# audio.net
KiCad netlist of a schematic drawn in Altium Designer
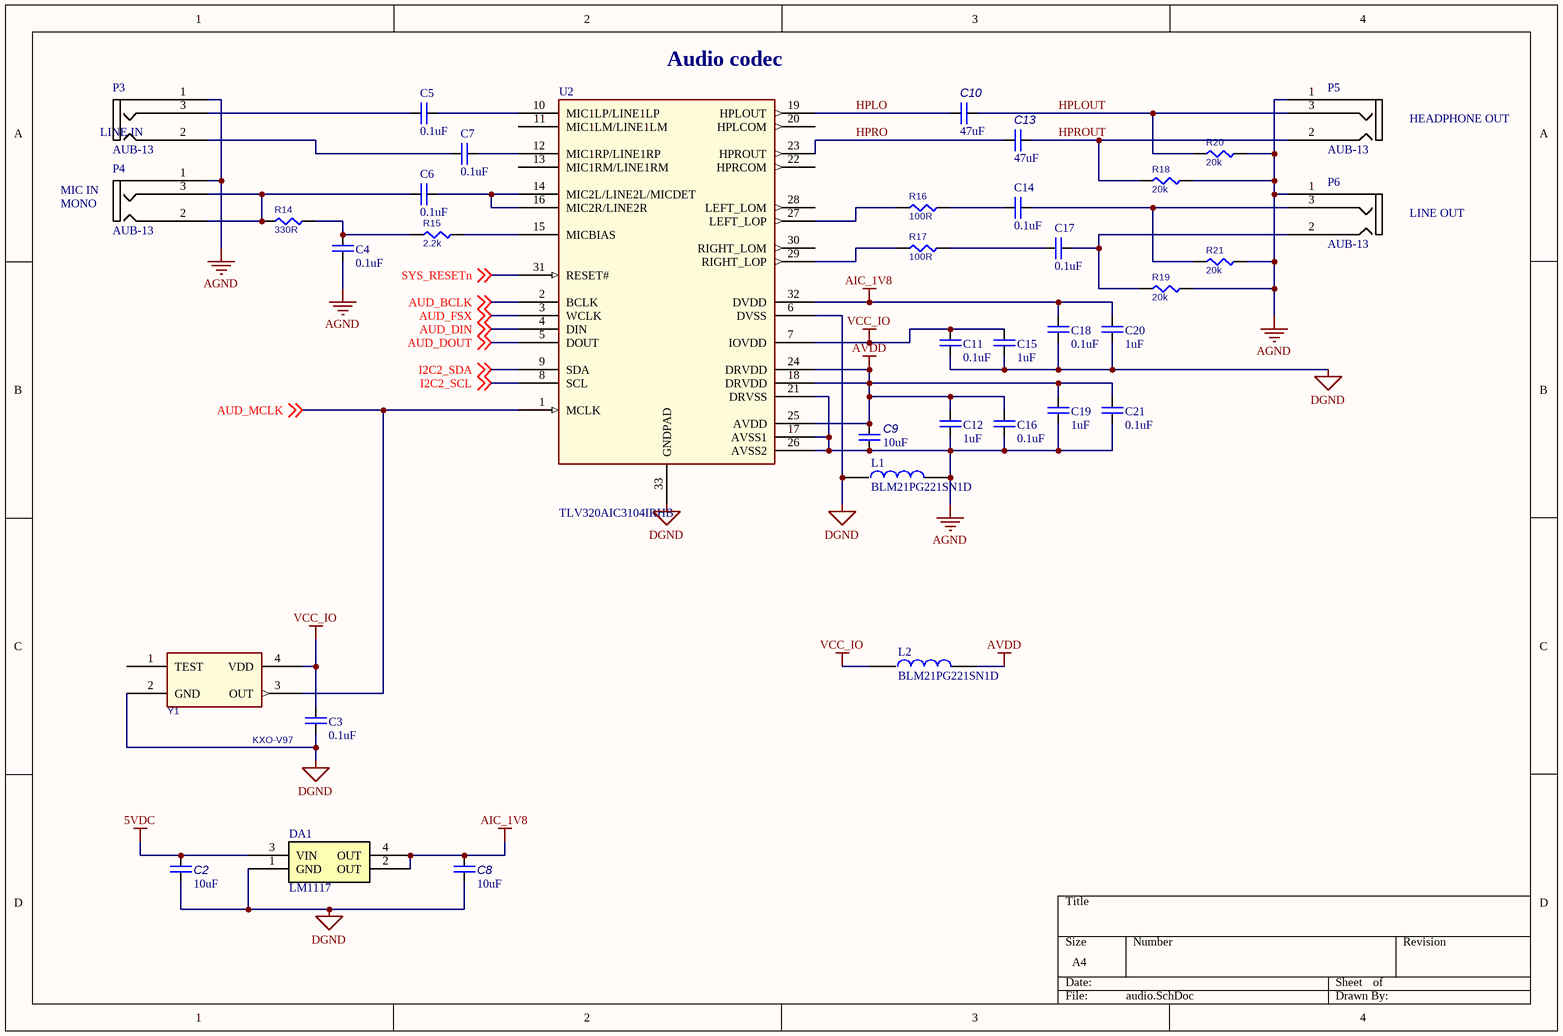
[diagram p0: audio.SchDoc]

(export (version "E")
  (design (tool "Eeschema 10.0.6"))
  (components
    (comp (ref "C2")
      (value "10uF")
      (footprint "CC2012-0805")
      (description "C0805")
      (libsource (lib "usomiq-audio") (part "C0805"))
    )
    (comp (ref "C3")
      (value "0.1uF")
      (footprint "CHIP0603")
      (description "Ceramic capacitor C0603")
      (fields (field (name "Comment") "C0603"))
      (libsource (lib "usomiq-audio") (part "C0603"))
    )
    (comp (ref "C4")
      (value "0.1uF")
      (footprint "CHIP0603")
      (description "Ceramic capacitor C0603")
      (fields (field (name "Comment") "C0603"))
      (libsource (lib "usomiq-audio") (part "C0603"))
    )
    (comp (ref "C5")
      (value "0.1uF")
      (footprint "CHIP0603")
      (description "Ceramic capacitor C0603")
      (fields (field (name "Comment") "C0603"))
      (libsource (lib "usomiq-audio") (part "C0603"))
    )
    (comp (ref "C6")
      (value "0.1uF")
      (footprint "CHIP0603")
      (description "Ceramic capacitor C0603")
      (fields (field (name "Comment") "C0603"))
      (libsource (lib "usomiq-audio") (part "C0603"))
    )
    (comp (ref "C7")
      (value "0.1uF")
      (footprint "CHIP0603")
      (description "Ceramic capacitor C0603")
      (fields (field (name "Comment") "C0603"))
      (libsource (lib "usomiq-audio") (part "C0603"))
    )
    (comp (ref "C8")
      (value "10uF")
      (footprint "CC2012-0805")
      (description "C0805")
      (libsource (lib "usomiq-audio") (part "C0805"))
    )
    (comp (ref "C9")
      (value "10uF")
      (footprint "CC2012-0805")
      (description "C0805")
      (libsource (lib "usomiq-audio") (part "C0805"))
    )
    (comp (ref "C10")
      (value "47uF")
      (footprint "CC3216-1206")
      (description "C1206")
      (libsource (lib "usomiq-audio") (part "C1206"))
    )
    (comp (ref "C11")
      (value "0.1uF")
      (footprint "CHIP0603")
      (description "Ceramic capacitor C0603")
      (fields (field (name "Comment") "C0603"))
      (libsource (lib "usomiq-audio") (part "C0603"))
    )
    (comp (ref "C12")
      (value "1uF")
      (footprint "CHIP0603")
      (description "Ceramic capacitor C0603")
      (fields (field (name "Comment") "C0603"))
      (libsource (lib "usomiq-audio") (part "C0603"))
    )
    (comp (ref "C13")
      (value "47uF")
      (footprint "CC3216-1206")
      (description "C1206")
      (libsource (lib "usomiq-audio") (part "C1206"))
    )
    (comp (ref "C14")
      (value "0.1uF")
      (footprint "CHIP0603")
      (description "Ceramic capacitor C0603")
      (fields (field (name "Comment") "C0603"))
      (libsource (lib "usomiq-audio") (part "C0603"))
    )
    (comp (ref "C15")
      (value "1uF")
      (footprint "CHIP0603")
      (description "Ceramic capacitor C0603")
      (fields (field (name "Comment") "C0603"))
      (libsource (lib "usomiq-audio") (part "C0603"))
    )
    (comp (ref "C16")
      (value "0.1uF")
      (footprint "CHIP0603")
      (description "Ceramic capacitor C0603")
      (fields (field (name "Comment") "C0603"))
      (libsource (lib "usomiq-audio") (part "C0603"))
    )
    (comp (ref "C17")
      (value "0.1uF")
      (footprint "CHIP0603")
      (description "Ceramic capacitor C0603")
      (fields (field (name "Comment") "C0603"))
      (libsource (lib "usomiq-audio") (part "C0603"))
    )
    (comp (ref "C18")
      (value "0.1uF")
      (footprint "CHIP0603")
      (description "Ceramic capacitor C0603")
      (fields (field (name "Comment") "C0603"))
      (libsource (lib "usomiq-audio") (part "C0603"))
    )
    (comp (ref "C19")
      (value "1uF")
      (footprint "CHIP0603")
      (description "Ceramic capacitor C0603")
      (fields (field (name "Comment") "C0603"))
      (libsource (lib "usomiq-audio") (part "C0603"))
    )
    (comp (ref "C20")
      (value "1uF")
      (footprint "CHIP0603")
      (description "Ceramic capacitor C0603")
      (fields (field (name "Comment") "C0603"))
      (libsource (lib "usomiq-audio") (part "C0603"))
    )
    (comp (ref "C21")
      (value "0.1uF")
      (footprint "CHIP0603")
      (description "Ceramic capacitor C0603")
      (fields (field (name "Comment") "C0603"))
      (libsource (lib "usomiq-audio") (part "C0603"))
    )
    (comp (ref "DA1")
      (value "LM1117")
      (footprint "SOT230P700X160-4N")
      (description "800mA Low-Dropout Linear Regulator")
      (fields (field (name "MANUFACTURER") "National"))
      (libsource (lib "usomiq-audio") (part "LM1117"))
    )
    (comp (ref "L1")
      (value "BLM21PG221SN1D")
      (footprint "Chip2PinSM127P600-8N")
      (fields (field (name "MANUFACTURER") "Murata"))
      (libsource (lib "usomiq-audio") (part "BLM21PG221SN1D"))
    )
    (comp (ref "L2")
      (value "BLM21PG221SN1D")
      (footprint "Chip2PinSM127P600-8N")
      (fields (field (name "MANUFACTURER") "Murata"))
      (libsource (lib "usomiq-audio") (part "BLM21PG221SN1D"))
    )
    (comp (ref "P3")
      (value "AUB-13")
      (footprint "AUB_13")
      (description "Audio connector mini-jack 3.5mm, 3 pins")
      (libsource (lib "usomiq-audio") (part "AUB-13"))
    )
    (comp (ref "P4")
      (value "AUB-13")
      (footprint "AUB_13")
      (description "Audio connector mini-jack 3.5mm, 3 pins")
      (libsource (lib "usomiq-audio") (part "AUB-13"))
    )
    (comp (ref "P5")
      (value "AUB-13")
      (footprint "AUB_13")
      (description "Audio connector mini-jack 3.5mm, 3 pins")
      (libsource (lib "usomiq-audio") (part "AUB-13"))
    )
    (comp (ref "P6")
      (value "AUB-13")
      (footprint "AUB_13")
      (description "Audio connector mini-jack 3.5mm, 3 pins")
      (libsource (lib "usomiq-audio") (part "AUB-13"))
    )
    (comp (ref "R14")
      (value "330R")
      (footprint "CHIP0603")
      (description "Resistor 0603")
      (fields (field (name "Comment") "R0603"))
      (libsource (lib "usomiq-audio") (part "R0603"))
    )
    (comp (ref "R15")
      (value "2.2k")
      (footprint "CHIP0603")
      (description "Resistor 0603")
      (fields (field (name "Comment") "R0603"))
      (libsource (lib "usomiq-audio") (part "R0603"))
    )
    (comp (ref "R16")
      (value "100R")
      (footprint "CHIP0603")
      (description "Resistor 0603")
      (fields (field (name "Comment") "R0603"))
      (libsource (lib "usomiq-audio") (part "R0603"))
    )
    (comp (ref "R17")
      (value "100R")
      (footprint "CHIP0603")
      (description "Resistor 0603")
      (fields (field (name "Comment") "R0603"))
      (libsource (lib "usomiq-audio") (part "R0603"))
    )
    (comp (ref "R18")
      (value "20k")
      (footprint "CHIP0603")
      (description "Resistor 0603")
      (fields (field (name "Comment") "R0603"))
      (libsource (lib "usomiq-audio") (part "R0603"))
    )
    (comp (ref "R19")
      (value "20k")
      (footprint "CHIP0603")
      (description "Resistor 0603")
      (fields (field (name "Comment") "R0603"))
      (libsource (lib "usomiq-audio") (part "R0603"))
    )
    (comp (ref "R20")
      (value "20k")
      (footprint "CHIP0603")
      (description "Resistor 0603")
      (fields (field (name "Comment") "R0603"))
      (libsource (lib "usomiq-audio") (part "R0603"))
    )
    (comp (ref "R21")
      (value "20k")
      (footprint "CHIP0603")
      (description "Resistor 0603")
      (fields (field (name "Comment") "R0603"))
      (libsource (lib "usomiq-audio") (part "R0603"))
    )
    (comp (ref "U2")
      (value "TLV320AIC3104")
      (footprint "QFN32")
      (description "LOW-POWER STEREO AUDIO CODEC FOR PORTABLE AUDIO/TELEPHONY")
      (fields (field (name "MANUFACTURER") "TI") (field (name "MAN P/N") "TLV320AIC3104IRHB"))
      (libsource (lib "usomiq-audio") (part "TLV320AIC3104"))
    )
    (comp (ref "Y1")
      (value "KXO-V97")
      (footprint "KXO_V97")
      (description "Quartz oscillator 7x5mm")
      (fields (field (name "MANUFACTURER") "Geyer"))
      (libsource (lib "usomiq-audio") (part "KXO-V97"))
    )
  )
  (nets
    (net (code "1") (name "/HPLO") (class "Default")
      (node (ref "C10") (pin "2") (pinfunction "2_2") (pintype "passive"))
      (node (ref "U2") (pin "19") (pinfunction "HPLOUT_19") (pintype "output"))
    )
    (net (code "2") (name "/HPLOUT") (class "Default")
      (node (ref "C10") (pin "1") (pinfunction "1_1") (pintype "passive"))
      (node (ref "P5") (pin "3") (pinfunction "LEFT_3") (pintype "passive"))
      (node (ref "R20") (pin "2") (pinfunction "2_2") (pintype "passive"))
    )
    (net (code "3") (name "/HPRO") (class "Default")
      (node (ref "C13") (pin "2") (pinfunction "2_2") (pintype "passive"))
      (node (ref "U2") (pin "23") (pinfunction "HPROUT_23") (pintype "output"))
    )
    (net (code "4") (name "/HPROUT") (class "Default")
      (node (ref "C13") (pin "1") (pinfunction "1_1") (pintype "passive"))
      (node (ref "P5") (pin "2") (pinfunction "RIGHT_2") (pintype "passive"))
      (node (ref "R18") (pin "2") (pinfunction "2_2") (pintype "passive"))
    )
    (net (code "5") (name "5VDC") (class "Default")
      (node (ref "C2") (pin "2") (pinfunction "2_2") (pintype "passive"))
      (node (ref "DA1") (pin "3") (pinfunction "VIN_3") (pintype "power_in"))
    )
    (net (code "6") (name "AGND") (class "Default")
      (node (ref "C12") (pin "2") (pinfunction "2_2") (pintype "passive"))
      (node (ref "C16") (pin "2") (pinfunction "2_2") (pintype "passive"))
      (node (ref "C19") (pin "2") (pinfunction "2_2") (pintype "passive"))
      (node (ref "C21") (pin "2") (pinfunction "2_2") (pintype "passive"))
      (node (ref "C4") (pin "1") (pinfunction "1_1") (pintype "passive"))
      (node (ref "C9") (pin "1") (pinfunction "1_1") (pintype "passive"))
      (node (ref "L1") (pin "2") (pinfunction "2_2") (pintype "passive"))
      (node (ref "P3") (pin "1") (pinfunction "GND_1") (pintype "passive"))
      (node (ref "P4") (pin "1") (pinfunction "GND_1") (pintype "passive"))
      (node (ref "P5") (pin "1") (pinfunction "GND_1") (pintype "passive"))
      (node (ref "P6") (pin "1") (pinfunction "GND_1") (pintype "passive"))
      (node (ref "R18") (pin "1") (pinfunction "1_1") (pintype "passive"))
      (node (ref "R19") (pin "1") (pinfunction "1_1") (pintype "passive"))
      (node (ref "R20") (pin "1") (pinfunction "1_1") (pintype "passive"))
      (node (ref "R21") (pin "1") (pinfunction "1_1") (pintype "passive"))
      (node (ref "U2") (pin "17") (pinfunction "AVSS1_17") (pintype "power_in"))
      (node (ref "U2") (pin "21") (pinfunction "DRVSS_21") (pintype "power_in"))
      (node (ref "U2") (pin "26") (pinfunction "AVSS2_26") (pintype "power_in"))
    )
    (net (code "7") (name "AIC_1V8") (class "Default")
      (node (ref "C18") (pin "1") (pinfunction "1_1") (pintype "passive"))
      (node (ref "C20") (pin "1") (pinfunction "1_1") (pintype "passive"))
      (node (ref "C8") (pin "2") (pinfunction "2_2") (pintype "passive"))
      (node (ref "DA1") (pin "2") (pinfunction "OUT_2") (pintype "power_in"))
      (node (ref "DA1") (pin "4") (pinfunction "OUT_4") (pintype "power_in"))
      (node (ref "U2") (pin "32") (pinfunction "DVDD_32") (pintype "power_in"))
    )
    (net (code "8") (name "AUD_BCLK") (class "Default")
      (node (ref "U2") (pin "2") (pinfunction "BCLK_2") (pintype "passive"))
    )
    (net (code "9") (name "AUD_DIN") (class "Default")
      (node (ref "U2") (pin "4") (pinfunction "DIN_4") (pintype "passive"))
    )
    (net (code "10") (name "AUD_DOUT") (class "Default")
      (node (ref "U2") (pin "5") (pinfunction "DOUT_5") (pintype "passive"))
    )
    (net (code "11") (name "AUD_FSX") (class "Default")
      (node (ref "U2") (pin "3") (pinfunction "WCLK_3") (pintype "passive"))
    )
    (net (code "12") (name "AUD_MCLK") (class "Default")
      (node (ref "U2") (pin "1") (pinfunction "MCLK_1") (pintype "input"))
      (node (ref "Y1") (pin "3") (pinfunction "OUT_3") (pintype "output"))
    )
    (net (code "13") (name "AVDD") (class "Default")
      (node (ref "C12") (pin "1") (pinfunction "1_1") (pintype "passive"))
      (node (ref "C16") (pin "1") (pinfunction "1_1") (pintype "passive"))
      (node (ref "C19") (pin "1") (pinfunction "1_1") (pintype "passive"))
      (node (ref "C21") (pin "1") (pinfunction "1_1") (pintype "passive"))
      (node (ref "C9") (pin "2") (pinfunction "2_2") (pintype "passive"))
      (node (ref "L2") (pin "2") (pinfunction "2_2") (pintype "passive"))
      (node (ref "U2") (pin "18") (pinfunction "DRVDD_18") (pintype "power_in"))
      (node (ref "U2") (pin "24") (pinfunction "DRVDD_24") (pintype "power_in"))
      (node (ref "U2") (pin "25") (pinfunction "AVDD_25") (pintype "power_in"))
    )
    (net (code "14") (name "DGND") (class "Default")
      (node (ref "C11") (pin "2") (pinfunction "2_2") (pintype "passive"))
      (node (ref "C15") (pin "2") (pinfunction "2_2") (pintype "passive"))
      (node (ref "C18") (pin "2") (pinfunction "2_2") (pintype "passive"))
      (node (ref "C2") (pin "1") (pinfunction "1_1") (pintype "passive"))
      (node (ref "C20") (pin "2") (pinfunction "2_2") (pintype "passive"))
      (node (ref "C3") (pin "2") (pinfunction "2_2") (pintype "passive"))
      (node (ref "C8") (pin "1") (pinfunction "1_1") (pintype "passive"))
      (node (ref "DA1") (pin "1") (pinfunction "GND_1") (pintype "power_in"))
      (node (ref "L1") (pin "1") (pinfunction "1_1") (pintype "passive"))
      (node (ref "U2") (pin "33") (pinfunction "GNDPAD_33") (pintype "power_in"))
      (node (ref "U2") (pin "6") (pinfunction "DVSS_6") (pintype "power_in"))
      (node (ref "Y1") (pin "2") (pinfunction "GND_2") (pintype "power_in"))
    )
    (net (code "15") (name "I2C2_SCL") (class "Default")
      (node (ref "U2") (pin "8") (pinfunction "SCL_8") (pintype "passive"))
    )
    (net (code "16") (name "I2C2_SDA") (class "Default")
      (node (ref "U2") (pin "9") (pinfunction "SDA_9") (pintype "passive"))
    )
    (net (code "17") (name "Net-(C4-Pad2)") (class "Default")
      (node (ref "C4") (pin "2") (pinfunction "2_2") (pintype "passive"))
      (node (ref "R14") (pin "2") (pinfunction "2_2") (pintype "passive"))
      (node (ref "R15") (pin "1") (pinfunction "1_1") (pintype "passive"))
    )
    (net (code "18") (name "Net-(C14-Pad1)") (class "Default")
      (node (ref "C14") (pin "1") (pinfunction "1_1") (pintype "passive"))
      (node (ref "R16") (pin "2") (pinfunction "2_2") (pintype "passive"))
    )
    (net (code "19") (name "Net-(C17-Pad1)") (class "Default")
      (node (ref "C17") (pin "1") (pinfunction "1_1") (pintype "passive"))
      (node (ref "R17") (pin "2") (pinfunction "2_2") (pintype "passive"))
    )
    (net (code "20") (name "Net-(P3-LEFT)") (class "Default")
      (node (ref "C5") (pin "1") (pinfunction "1_1") (pintype "passive"))
      (node (ref "P3") (pin "3") (pinfunction "LEFT_3") (pintype "passive"))
    )
    (net (code "21") (name "Net-(P3-RIGHT)") (class "Default")
      (node (ref "C7") (pin "1") (pinfunction "1_1") (pintype "passive"))
      (node (ref "P3") (pin "2") (pinfunction "RIGHT_2") (pintype "passive"))
    )
    (net (code "22") (name "Net-(P4-LEFT)") (class "Default")
      (node (ref "C6") (pin "1") (pinfunction "1_1") (pintype "passive"))
      (node (ref "P4") (pin "2") (pinfunction "RIGHT_2") (pintype "passive"))
      (node (ref "P4") (pin "3") (pinfunction "LEFT_3") (pintype "passive"))
      (node (ref "R14") (pin "1") (pinfunction "1_1") (pintype "passive"))
    )
    (net (code "23") (name "Net-(P6-LEFT)") (class "Default")
      (node (ref "C14") (pin "2") (pinfunction "2_2") (pintype "passive"))
      (node (ref "P6") (pin "3") (pinfunction "LEFT_3") (pintype "passive"))
      (node (ref "R21") (pin "2") (pinfunction "2_2") (pintype "passive"))
    )
    (net (code "24") (name "Net-(P6-RIGHT)") (class "Default")
      (node (ref "C17") (pin "2") (pinfunction "2_2") (pintype "passive"))
      (node (ref "P6") (pin "2") (pinfunction "RIGHT_2") (pintype "passive"))
      (node (ref "R19") (pin "2") (pinfunction "2_2") (pintype "passive"))
    )
    (net (code "25") (name "Net-(U2-LEFT_LOP)") (class "Default")
      (node (ref "R16") (pin "1") (pinfunction "1_1") (pintype "passive"))
      (node (ref "U2") (pin "27") (pinfunction "LEFT_LOP_27") (pintype "output"))
    )
    (net (code "26") (name "Net-(U2-MIC1LP{slash}LINE1LP)") (class "Default")
      (node (ref "C5") (pin "2") (pinfunction "2_2") (pintype "passive"))
      (node (ref "U2") (pin "10") (pinfunction "MIC1LP/LINE1LP_10") (pintype "passive"))
    )
    (net (code "27") (name "Net-(U2-MIC1RP{slash}LINE1RP)") (class "Default")
      (node (ref "C7") (pin "2") (pinfunction "2_2") (pintype "passive"))
      (node (ref "U2") (pin "12") (pinfunction "MIC1RP/LINE1RP_12") (pintype "passive"))
    )
    (net (code "28") (name "Net-(U2-MIC2L{slash}LINE2L{slash}MICDET)") (class "Default")
      (node (ref "C6") (pin "2") (pinfunction "2_2") (pintype "passive"))
      (node (ref "U2") (pin "14") (pinfunction "MIC2L/LINE2L/MICDET_14") (pintype "passive"))
      (node (ref "U2") (pin "16") (pinfunction "MIC2R/LINE2R_16") (pintype "passive"))
    )
    (net (code "29") (name "Net-(U2-MICBIAS)") (class "Default")
      (node (ref "R15") (pin "2") (pinfunction "2_2") (pintype "passive"))
      (node (ref "U2") (pin "15") (pinfunction "MICBIAS_15") (pintype "passive"))
    )
    (net (code "30") (name "Net-(U2-RIGHT_LOP)") (class "Default")
      (node (ref "R17") (pin "1") (pinfunction "1_1") (pintype "passive"))
      (node (ref "U2") (pin "29") (pinfunction "RIGHT_LOP_29") (pintype "output"))
    )
    (net (code "31") (name "SYS_RESETn") (class "Default")
      (node (ref "U2") (pin "31") (pinfunction "RESET#_31") (pintype "input"))
    )
    (net (code "32") (name "VCC_IO") (class "Default")
      (node (ref "C11") (pin "1") (pinfunction "1_1") (pintype "passive"))
      (node (ref "C15") (pin "1") (pinfunction "1_1") (pintype "passive"))
      (node (ref "C3") (pin "1") (pinfunction "1_1") (pintype "passive"))
      (node (ref "L2") (pin "1") (pinfunction "1_1") (pintype "passive"))
      (node (ref "U2") (pin "7") (pinfunction "IOVDD_7") (pintype "power_in"))
      (node (ref "Y1") (pin "4") (pinfunction "VDD_4") (pintype "power_in"))
    )
    (net (code "33") (name "unconnected-(U2-HPLCOM-Pad20)") (class "Default")
      (node (ref "U2") (pin "20") (pinfunction "HPLCOM_20") (pintype "output"))
    )
    (net (code "34") (name "unconnected-(U2-HPRCOM-Pad22)") (class "Default")
      (node (ref "U2") (pin "22") (pinfunction "HPRCOM_22") (pintype "output"))
    )
    (net (code "35") (name "unconnected-(U2-LEFT_LOM-Pad28)") (class "Default")
      (node (ref "U2") (pin "28") (pinfunction "LEFT_LOM_28") (pintype "output"))
    )
    (net (code "36") (name "unconnected-(U2-MIC1LM{slash}LINE1LM-Pad11)") (class "Default")
      (node (ref "U2") (pin "11") (pinfunction "MIC1LM/LINE1LM_11") (pintype "passive"))
    )
    (net (code "37") (name "unconnected-(U2-MIC1RM{slash}LINE1RM-Pad13)") (class "Default")
      (node (ref "U2") (pin "13") (pinfunction "MIC1RM/LINE1RM_13") (pintype "passive"))
    )
    (net (code "38") (name "unconnected-(U2-RIGHT_LOM-Pad30)") (class "Default")
      (node (ref "U2") (pin "30") (pinfunction "RIGHT_LOM_30") (pintype "output"))
    )
    (net (code "39") (name "unconnected-(Y1-TEST-Pad1)") (class "Default")
      (node (ref "Y1") (pin "1") (pinfunction "TEST_1") (pintype "passive"))
    )
  )
)
